# Top.net
KiCad netlist of a schematic drawn in Altium Designer
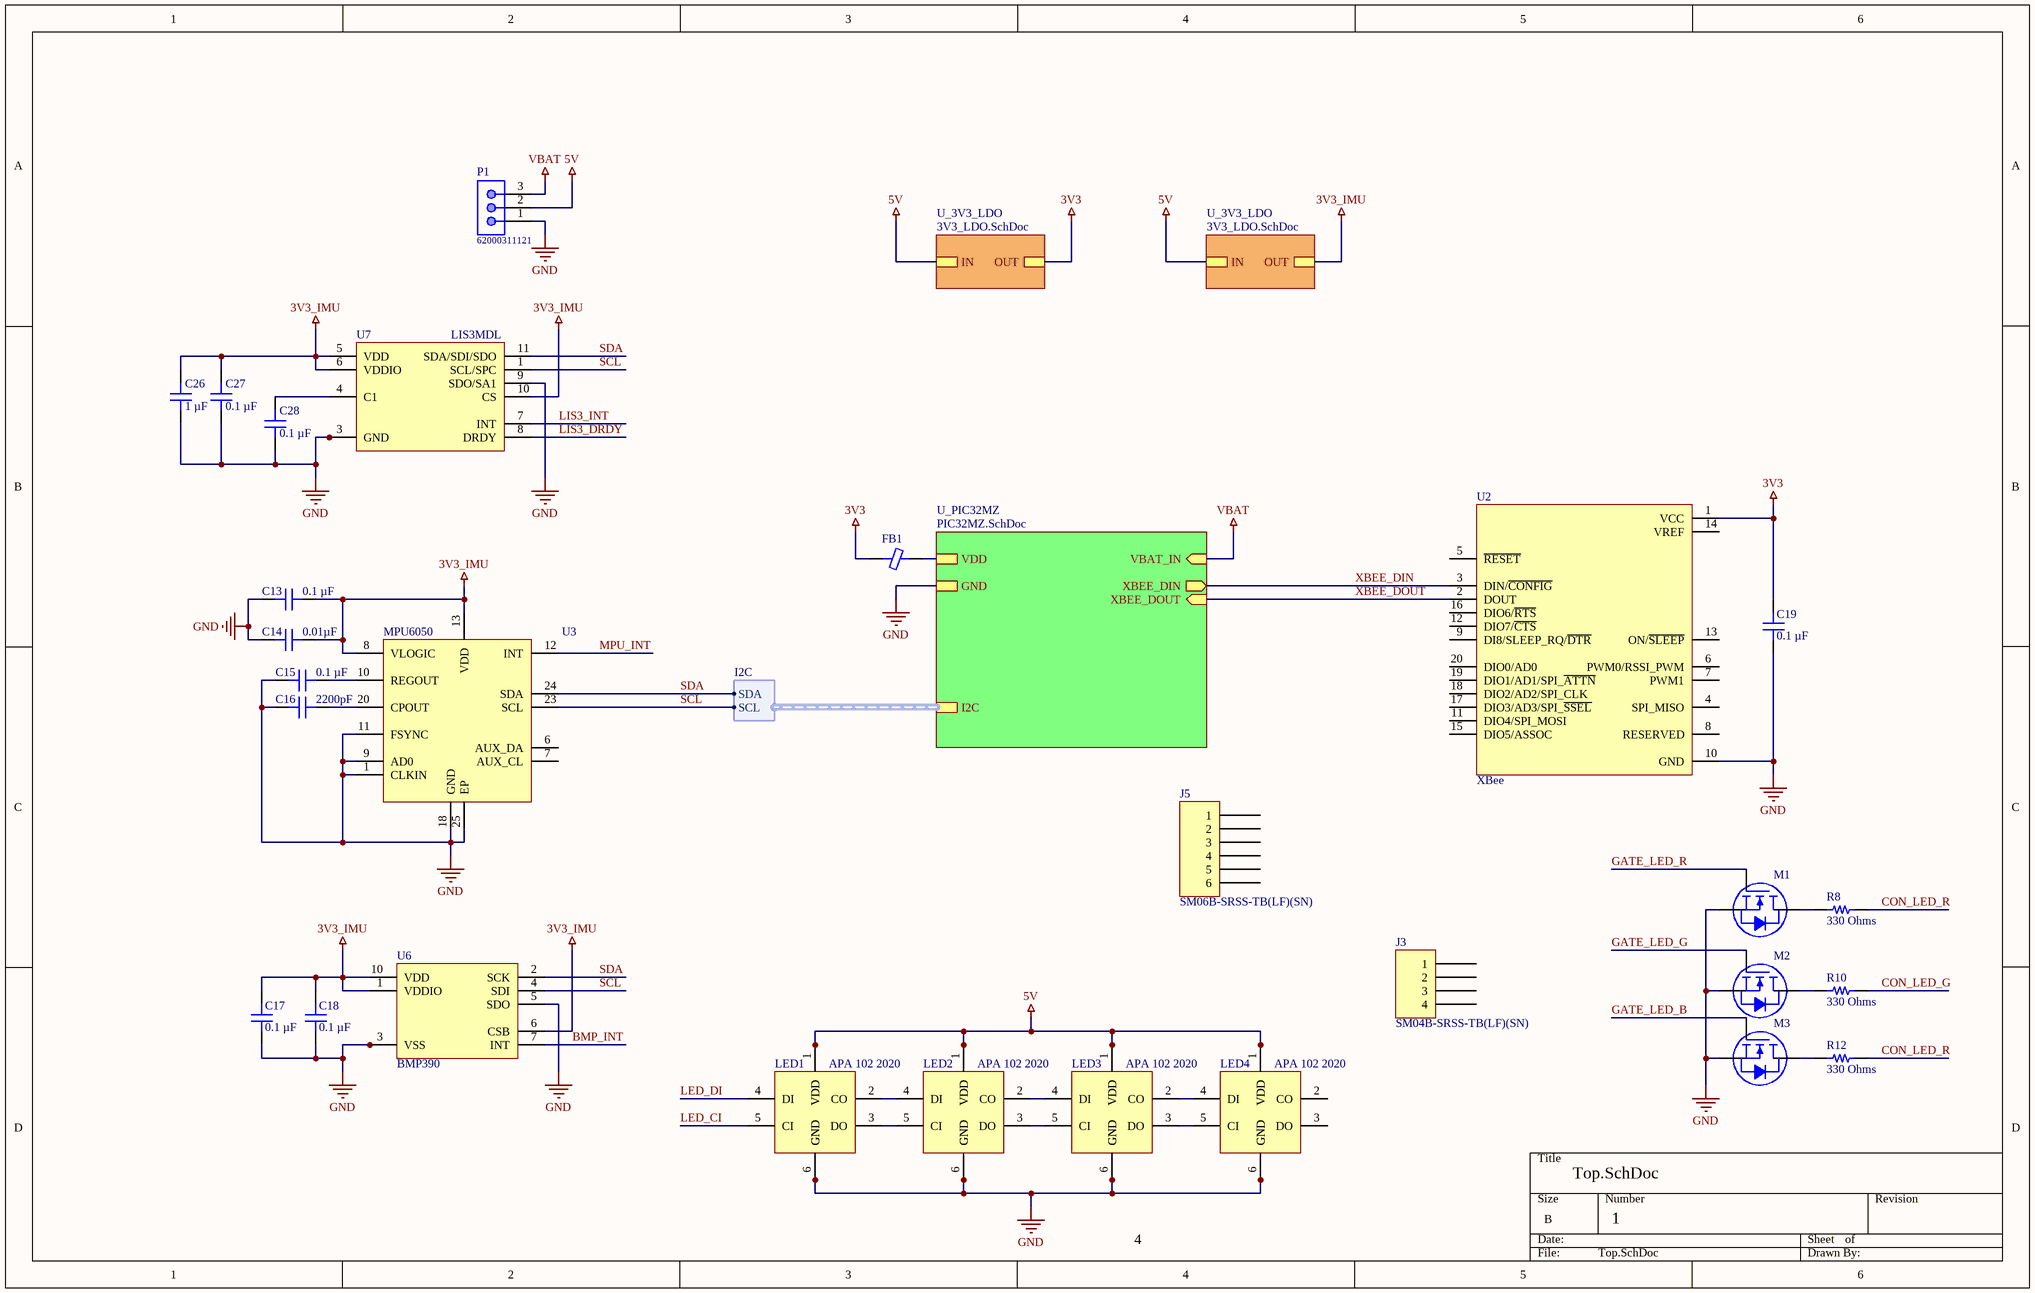
[diagram p0: Top.SchDoc]

(export (version "E")
  (design (tool "Eeschema 10.0.6"))
  (components
    (comp (ref "C13")
      (value "0.1 µF")
      (footprint "CAP 0402_1005")
      (description "CAP CER 0.1UF 16V X7R 0402")
      (fields (field (name "PART NUMBER") "C0402C104K4RACAUTO") (field (name "MANUFACTURER") "KEMET"))
      (libsource (lib "Celestial Altium Library - altium_library") (part "Capacitor"))
    )
    (comp (ref "C14")
      (value "0.01µF")
      (footprint "CAP 0603_1608")
      (description "CAP CER 0.01UF 250V X7R 0603")
      (fields (field (name "PART NUMBER") "C0603C103KARACAUTO") (field (name "MANUFACTURER") "KEMET"))
      (libsource (lib "Celestial Altium Library - altium_library") (part "Capacitor"))
    )
    (comp (ref "C15")
      (value "0.1 µF")
      (footprint "CAP 0402_1005")
      (description "CAP CER 0.1UF 16V X7R 0402")
      (fields (field (name "PART NUMBER") "C0402C104K4RACAUTO") (field (name "MANUFACTURER") "KEMET"))
      (libsource (lib "Celestial Altium Library - altium_library") (part "Capacitor"))
    )
    (comp (ref "C16")
      (value "2200pF")
      (footprint "CAP 0603_1608")
      (description "CAP CER 2200PF 50V 0603 EPOXY")
      (fields
        (field (name "PART NUMBER") "CGA3E2X8R1H222M080AD")
        (field (name "MANUFACTURER") "TDK Corporation")
      )
      (libsource (lib "Celestial Altium Library - altium_library") (part "Capacitor"))
    )
    (comp (ref "C17")
      (value "0.1 µF")
      (footprint "CAP 0402_1005")
      (description "CAP CER 0.1UF 16V X7R 0402")
      (fields (field (name "PART NUMBER") "C0402C104K4RACAUTO") (field (name "MANUFACTURER") "KEMET"))
      (libsource (lib "Celestial Altium Library - altium_library") (part "Capacitor"))
    )
    (comp (ref "C18")
      (value "0.1 µF")
      (footprint "CAP 0402_1005")
      (description "CAP CER 0.1UF 16V X7R 0402")
      (fields (field (name "PART NUMBER") "C0402C104K4RACAUTO") (field (name "MANUFACTURER") "KEMET"))
      (libsource (lib "Celestial Altium Library - altium_library") (part "Capacitor"))
    )
    (comp (ref "C19")
      (value "0.1 µF")
      (footprint "CAP 0402_1005")
      (description "CAP CER 0.1UF 16V X7R 0402")
      (fields (field (name "PART NUMBER") "C0402C104K4RACAUTO") (field (name "MANUFACTURER") "KEMET"))
      (libsource (lib "Celestial Altium Library - altium_library") (part "Capacitor"))
    )
    (comp (ref "C26")
      (value "1 µF")
      (footprint "CAP 0402_1005")
      (description "CAP CER 0.1UF 16V X7R 0402")
      (fields (field (name "PART NUMBER") "C0402C104K4RACAUTO") (field (name "MANUFACTURER") "KEMET"))
      (libsource (lib "Celestial Altium Library - altium_library") (part "Capacitor"))
    )
    (comp (ref "C27")
      (value "0.1 µF")
      (footprint "CAP 0402_1005")
      (description "CAP CER 0.1UF 16V X7R 0402")
      (fields (field (name "PART NUMBER") "C0402C104K4RACAUTO") (field (name "MANUFACTURER") "KEMET"))
      (libsource (lib "Celestial Altium Library - altium_library") (part "Capacitor"))
    )
    (comp (ref "C28")
      (value "0.1 µF")
      (footprint "CAP 0402_1005")
      (description "CAP CER 0.1UF 16V X7R 0402")
      (fields (field (name "PART NUMBER") "C0402C104K4RACAUTO") (field (name "MANUFACTURER") "KEMET"))
      (libsource (lib "Celestial Altium Library - altium_library") (part "Capacitor"))
    )
    (comp (ref "FB1")
      (value "~")
      (footprint "FER 0805_2012")
      (description "FERRITE BEAD 0805 1LN")
      (fields
        (field (name "PART NUMBER") "2508051017Y0")
        (field (name "MANUFACTURER") "Fair-Rite Products Corp.")
      )
      (libsource (lib "Celestial Altium Library - altium_library") (part "Ferrite Chip"))
    )
    (comp (ref "J3")
      (value "SM04B-SRSS-TB(LF)(SN)")
      (footprint "JST SM04B-SRSS-TB")
      (description "CONN HEADER SMD R/A 4POS 1MM")
      (fields (field (name "MANUFACTURER") "JST Sales America Inc."))
      (libsource (lib "Celestial Altium Library - altium_library") (part "4 Pin"))
    )
    (comp (ref "J5")
      (value "SM06B-SRSS-TB(LF)(SN)")
      (footprint "JST SM06B-SRSS-TB")
      (description "CONN HEADER SMD R/A 6POS 1MM")
      (fields (field (name "MANUFACTURER") "JST Sales America Inc."))
      (libsource (lib "Celestial Altium Library - altium_library") (part "6 Pin"))
    )
    (comp (ref "LED1")
      (value "APA 102 2020")
      (footprint "LED_APA-102-2020-256-8")
      (description "8-pin type LED three-color RGB Dimming control")
      (fields (field (name "MP") "APA-102-2020-256-8") (field (name "MF") "iPixel LED Light Co."))
      (libsource (lib "IC") (part "APA-102-2020-256-8"))
    )
    (comp (ref "LED2")
      (value "APA 102 2020")
      (footprint "LED_APA-102-2020-256-8")
      (description "8-pin type LED three-color RGB Dimming control")
      (fields (field (name "MP") "APA-102-2020-256-8") (field (name "MF") "iPixel LED Light Co."))
      (libsource (lib "IC") (part "APA-102-2020-256-8"))
    )
    (comp (ref "LED3")
      (value "APA 102 2020")
      (footprint "LED_APA-102-2020-256-8")
      (description "8-pin type LED three-color RGB Dimming control")
      (fields (field (name "MP") "APA-102-2020-256-8") (field (name "MF") "iPixel LED Light Co."))
      (libsource (lib "IC") (part "APA-102-2020-256-8"))
    )
    (comp (ref "LED4")
      (value "APA 102 2020")
      (footprint "LED_APA-102-2020-256-8")
      (description "8-pin type LED three-color RGB Dimming control")
      (fields (field (name "MP") "APA-102-2020-256-8") (field (name "MF") "iPixel LED Light Co."))
      (libsource (lib "IC") (part "APA-102-2020-256-8"))
    )
    (comp (ref "M1")
      (value "BSS123-7-F")
      (footprint "DIODES SOT-23-3")
      (description "MOSFET N-CH 100V 170MA SOT23-3")
      (fields (field (name "MANUFACTURER") "Diodes Incorporated"))
      (libsource (lib "Celestial Altium Library - altium_library") (part "DIODES INC MOSFET N-CH SOT-23-3"))
    )
    (comp (ref "M2")
      (value "BSS123-7-F")
      (footprint "DIODES SOT-23-3")
      (description "MOSFET N-CH 100V 170MA SOT23-3")
      (fields (field (name "MANUFACTURER") "Diodes Incorporated"))
      (libsource (lib "Celestial Altium Library - altium_library") (part "DIODES INC MOSFET N-CH SOT-23-3"))
    )
    (comp (ref "M3")
      (value "BSS123-7-F")
      (footprint "DIODES SOT-23-3")
      (description "MOSFET N-CH 100V 170MA SOT23-3")
      (fields (field (name "MANUFACTURER") "Diodes Incorporated"))
      (libsource (lib "Celestial Altium Library - altium_library") (part "DIODES INC MOSFET N-CH SOT-23-3"))
    )
    (comp (ref "P1")
      (value "62000311121")
      (footprint "62000311121")
      (description "WR-PHD Pin Header, THT, pitch 2mm, Single Row, Vertical, 3p")
      (fields (field (name "MANUFACTURER") "Wurth Elektronik"))
      (libsource (lib "Altium_WR-PHD") (part "62000311121"))
    )
    (comp (ref "R8")
      (value "330 Ohms")
      (footprint "RES 0603_1608")
      (description "RES 10K OHM 0.1% 1/16W 0603")
      (fields
        (field (name "PART NUMBER") "RNCS0603BKE10K0")
        (field (name "MANUFACTURER") "Stackpole Electronics Inc")
      )
      (libsource (lib "Celestial Altium Library - altium_library") (part "Resistor"))
    )
    (comp (ref "R10")
      (value "330 Ohms")
      (footprint "RES 0603_1608")
      (description "RES 10K OHM 0.1% 1/16W 0603")
      (fields
        (field (name "PART NUMBER") "RNCS0603BKE10K0")
        (field (name "MANUFACTURER") "Stackpole Electronics Inc")
      )
      (libsource (lib "Celestial Altium Library - altium_library") (part "Resistor"))
    )
    (comp (ref "R12")
      (value "330 Ohms")
      (footprint "RES 0603_1608")
      (description "RES 10K OHM 0.1% 1/16W 0603")
      (fields
        (field (name "PART NUMBER") "RNCS0603BKE10K0")
        (field (name "MANUFACTURER") "Stackpole Electronics Inc")
      )
      (libsource (lib "Celestial Altium Library - altium_library") (part "Resistor"))
    )
    (comp (ref "U2")
      (value "XBee")
      (footprint "XBee -SMD Header")
      (description "802.15.4 Transceiver Module 2.4GHz Antenna Not Included, U.FL Through Hole")
      (libsource (lib "IC") (part "XBee SMD Header"))
    )
    (comp (ref "U3") (value "MPU6050") (footprint "IC_MPU6050") (libsource (lib "IC") (part "MPU6050")))
    (comp (ref "U6")
      (value "BMP390")
      (footprint "BMP390L")
      (description "Altimeter")
      (libsource (lib "IC") (part "BMP390"))
    )
    (comp (ref "U7")
      (value "LIS3MDL")
      (footprint "LGA12_ST")
      (description "Magnetometer")
      (libsource (lib "IC") (part "LIS3MDL"))
    )
  )
  (nets
    (net (code "2") (name "/BMP_INT") (class "Default")
      (node (ref "U6") (pin "7") (pinfunction "INT_7") (pintype "passive"))
    )
    (net (code "3") (name "/CON_LED_G") (class "Default")
      (node (ref "R10") (pin "2") (pinfunction "2_2") (pintype "passive"))
    )
    (net (code "4") (name "/CON_LED_R") (class "Default")
      (node (ref "R12") (pin "2") (pinfunction "2_2") (pintype "passive"))
      (node (ref "R8") (pin "2") (pinfunction "2_2") (pintype "passive"))
    )
    (net (code "5") (name "/GATE_LED_B") (class "Default")
      (node (ref "M3") (pin "1") (pinfunction "G_1") (pintype "passive"))
    )
    (net (code "6") (name "/GATE_LED_G") (class "Default")
      (node (ref "M2") (pin "1") (pinfunction "G_1") (pintype "passive"))
    )
    (net (code "7") (name "/GATE_LED_R") (class "Default")
      (node (ref "M1") (pin "1") (pinfunction "G_1") (pintype "passive"))
    )
    (net (code "8") (name "/LED_CI") (class "Default")
      (node (ref "LED1") (pin "5") (pinfunction "CI_5") (pintype "passive"))
    )
    (net (code "9") (name "/LED_DI") (class "Default")
      (node (ref "LED1") (pin "4") (pinfunction "DI_4") (pintype "passive"))
    )
    (net (code "10") (name "/LIS3_DRDY") (class "Default")
      (node (ref "U7") (pin "8") (pinfunction "DRDY_8") (pintype "passive"))
    )
    (net (code "11") (name "/LIS3_INT") (class "Default")
      (node (ref "U7") (pin "7") (pinfunction "INT_7") (pintype "passive"))
    )
    (net (code "12") (name "/MPU_INT") (class "Default")
      (node (ref "U3") (pin "12") (pinfunction "INT_12") (pintype "passive"))
    )
    (net (code "13") (name "/SCL") (class "Default")
      (node (ref "U3") (pin "23") (pinfunction "SCL_23") (pintype "passive"))
      (node (ref "U6") (pin "4") (pinfunction "SDI_4") (pintype "passive"))
      (node (ref "U7") (pin "1") (pinfunction "SCL/SPC_1") (pintype "passive"))
    )
    (net (code "14") (name "/SDA") (class "Default")
      (node (ref "U3") (pin "24") (pinfunction "SDA_24") (pintype "passive"))
      (node (ref "U6") (pin "2") (pinfunction "SCK_2") (pintype "passive"))
      (node (ref "U7") (pin "11") (pinfunction "SDA/SDI/SDO_11") (pintype "passive"))
    )
    (net (code "15") (name "/VDD") (class "Default")
      (node (ref "FB1") (pin "2") (pinfunction "2_2") (pintype "passive"))
    )
    (net (code "16") (name "/XBEE_DIN") (class "Default")
      (node (ref "U2") (pin "3") (pinfunction "DIN/~{CONFIG}_3") (pintype "passive"))
    )
    (net (code "17") (name "/XBEE_DOUT") (class "Default")
      (node (ref "U2") (pin "2") (pinfunction "DOUT_2") (pintype "passive"))
    )
    (net (code "19") (name "3V3") (class "Default")
      (node (ref "C19") (pin "2") (pinfunction "2_2") (pintype "passive"))
      (node (ref "FB1") (pin "1") (pinfunction "1_1") (pintype "passive"))
      (node (ref "U2") (pin "1") (pinfunction "VCC_1") (pintype "power_in"))
    )
    (net (code "20") (name "3V3_IMU") (class "Default")
      (node (ref "C13") (pin "1") (pinfunction "1_1") (pintype "passive"))
      (node (ref "C14") (pin "2") (pinfunction "2_2") (pintype "passive"))
      (node (ref "C17") (pin "2") (pinfunction "2_2") (pintype "passive"))
      (node (ref "C18") (pin "2") (pinfunction "2_2") (pintype "passive"))
      (node (ref "C26") (pin "1") (pinfunction "1_1") (pintype "passive"))
      (node (ref "C27") (pin "1") (pinfunction "1_1") (pintype "passive"))
      (node (ref "U3") (pin "13") (pinfunction "VDD_13") (pintype "passive"))
      (node (ref "U3") (pin "8") (pinfunction "VLOGIC_8") (pintype "passive"))
      (node (ref "U6") (pin "1") (pinfunction "VDDIO_1") (pintype "passive"))
      (node (ref "U6") (pin "10") (pinfunction "VDD_10") (pintype "passive"))
      (node (ref "U6") (pin "6") (pinfunction "CSB_6") (pintype "passive"))
      (node (ref "U7") (pin "10") (pinfunction "CS_10") (pintype "passive"))
      (node (ref "U7") (pin "5") (pinfunction "VDD_5") (pintype "passive"))
      (node (ref "U7") (pin "6") (pinfunction "VDDIO_6") (pintype "passive"))
    )
    (net (code "21") (name "5V") (class "Default")
      (node (ref "LED1") (pin "1") (pinfunction "VDD_1") (pintype "power_in"))
      (node (ref "LED1") (pin "8") (pinfunction "VDD_8") (pintype "power_in"))
      (node (ref "LED2") (pin "1") (pinfunction "VDD_1") (pintype "power_in"))
      (node (ref "LED2") (pin "8") (pinfunction "VDD_8") (pintype "power_in"))
      (node (ref "LED3") (pin "1") (pinfunction "VDD_1") (pintype "power_in"))
      (node (ref "LED3") (pin "8") (pinfunction "VDD_8") (pintype "power_in"))
      (node (ref "LED4") (pin "1") (pinfunction "VDD_1") (pintype "power_in"))
      (node (ref "LED4") (pin "8") (pinfunction "VDD_8") (pintype "power_in"))
      (node (ref "P1") (pin "2") (pinfunction "2_2") (pintype "passive"))
    )
    (net (code "22") (name "GND") (class "Default")
      (node (ref "C13") (pin "2") (pinfunction "2_2") (pintype "passive"))
      (node (ref "C14") (pin "1") (pinfunction "1_1") (pintype "passive"))
      (node (ref "C15") (pin "2") (pinfunction "2_2") (pintype "passive"))
      (node (ref "C16") (pin "2") (pinfunction "2_2") (pintype "passive"))
      (node (ref "C17") (pin "1") (pinfunction "1_1") (pintype "passive"))
      (node (ref "C18") (pin "1") (pinfunction "1_1") (pintype "passive"))
      (node (ref "C19") (pin "1") (pinfunction "1_1") (pintype "passive"))
      (node (ref "C26") (pin "2") (pinfunction "2_2") (pintype "passive"))
      (node (ref "C27") (pin "2") (pinfunction "2_2") (pintype "passive"))
      (node (ref "C28") (pin "2") (pinfunction "2_2") (pintype "passive"))
      (node (ref "LED1") (pin "6") (pinfunction "GND_6") (pintype "power_in"))
      (node (ref "LED1") (pin "7") (pinfunction "GND_7") (pintype "power_in"))
      (node (ref "LED2") (pin "6") (pinfunction "GND_6") (pintype "power_in"))
      (node (ref "LED2") (pin "7") (pinfunction "GND_7") (pintype "power_in"))
      (node (ref "LED3") (pin "6") (pinfunction "GND_6") (pintype "power_in"))
      (node (ref "LED3") (pin "7") (pinfunction "GND_7") (pintype "power_in"))
      (node (ref "LED4") (pin "6") (pinfunction "GND_6") (pintype "power_in"))
      (node (ref "LED4") (pin "7") (pinfunction "GND_7") (pintype "power_in"))
      (node (ref "M1") (pin "2") (pinfunction "S_2") (pintype "passive"))
      (node (ref "M2") (pin "2") (pinfunction "S_2") (pintype "passive"))
      (node (ref "M3") (pin "2") (pinfunction "S_2") (pintype "passive"))
      (node (ref "P1") (pin "1") (pinfunction "1_1") (pintype "passive"))
      (node (ref "U2") (pin "10") (pinfunction "GND_10") (pintype "power_in"))
      (node (ref "U3") (pin "1") (pinfunction "CLKIN_1") (pintype "passive"))
      (node (ref "U3") (pin "11") (pinfunction "FSYNC_11") (pintype "passive"))
      (node (ref "U3") (pin "18") (pinfunction "GND_18") (pintype "passive"))
      (node (ref "U3") (pin "25") (pinfunction "EP_25") (pintype "passive"))
      (node (ref "U3") (pin "9") (pinfunction "AD0_9") (pintype "passive"))
      (node (ref "U6") (pin "3") (pinfunction "VSS_3") (pintype "passive"))
      (node (ref "U6") (pin "5") (pinfunction "SDO_5") (pintype "passive"))
      (node (ref "U6") (pin "8") (pinfunction "VSS_8") (pintype "passive"))
      (node (ref "U6") (pin "9") (pinfunction "VSS_9") (pintype "passive"))
      (node (ref "U7") (pin "12") (pinfunction "Reserved_12") (pintype "passive"))
      (node (ref "U7") (pin "2") (pinfunction "Reserved_2") (pintype "passive"))
      (node (ref "U7") (pin "3") (pinfunction "GND_3") (pintype "passive"))
      (node (ref "U7") (pin "9") (pinfunction "SDO/SA1_9") (pintype "passive"))
    )
    (net (code "23") (name "Net-(LED1-CO)") (class "Default")
      (node (ref "LED1") (pin "2") (pinfunction "CO_2") (pintype "passive"))
      (node (ref "LED2") (pin "4") (pinfunction "DI_4") (pintype "passive"))
    )
    (net (code "24") (name "Net-(LED1-DO)") (class "Default")
      (node (ref "LED1") (pin "3") (pinfunction "DO_3") (pintype "passive"))
      (node (ref "LED2") (pin "5") (pinfunction "CI_5") (pintype "passive"))
    )
    (net (code "25") (name "Net-(LED2-CO)") (class "Default")
      (node (ref "LED2") (pin "2") (pinfunction "CO_2") (pintype "passive"))
      (node (ref "LED3") (pin "4") (pinfunction "DI_4") (pintype "passive"))
    )
    (net (code "26") (name "Net-(LED2-DO)") (class "Default")
      (node (ref "LED2") (pin "3") (pinfunction "DO_3") (pintype "passive"))
      (node (ref "LED3") (pin "5") (pinfunction "CI_5") (pintype "passive"))
    )
    (net (code "27") (name "Net-(LED3-CO)") (class "Default")
      (node (ref "LED3") (pin "2") (pinfunction "CO_2") (pintype "passive"))
      (node (ref "LED4") (pin "4") (pinfunction "DI_4") (pintype "passive"))
    )
    (net (code "28") (name "Net-(LED3-DO)") (class "Default")
      (node (ref "LED3") (pin "3") (pinfunction "DO_3") (pintype "passive"))
      (node (ref "LED4") (pin "5") (pinfunction "CI_5") (pintype "passive"))
    )
    (net (code "29") (name "Net-(M1-D)") (class "Default")
      (node (ref "M1") (pin "3") (pinfunction "D_3") (pintype "passive"))
      (node (ref "R8") (pin "1") (pinfunction "1_1") (pintype "passive"))
    )
    (net (code "30") (name "Net-(M2-D)") (class "Default")
      (node (ref "M2") (pin "3") (pinfunction "D_3") (pintype "passive"))
      (node (ref "R10") (pin "1") (pinfunction "1_1") (pintype "passive"))
    )
    (net (code "31") (name "Net-(M3-D)") (class "Default")
      (node (ref "M3") (pin "3") (pinfunction "D_3") (pintype "passive"))
      (node (ref "R12") (pin "1") (pinfunction "1_1") (pintype "passive"))
    )
    (net (code "32") (name "Net-(U3-CPOUT)") (class "Default")
      (node (ref "C16") (pin "1") (pinfunction "1_1") (pintype "passive"))
      (node (ref "U3") (pin "20") (pinfunction "CPOUT_20") (pintype "passive"))
    )
    (net (code "33") (name "Net-(U3-REGOUT)") (class "Default")
      (node (ref "C15") (pin "1") (pinfunction "1_1") (pintype "passive"))
      (node (ref "U3") (pin "10") (pinfunction "REGOUT_10") (pintype "passive"))
    )
    (net (code "34") (name "Net-(U7-C1)") (class "Default")
      (node (ref "C28") (pin "1") (pinfunction "1_1") (pintype "passive"))
      (node (ref "U7") (pin "4") (pinfunction "C1_4") (pintype "passive"))
    )
    (net (code "35") (name "VBAT") (class "Default")
      (node (ref "P1") (pin "3") (pinfunction "3_3") (pintype "passive"))
    )
    (net (code "36") (name "unconnected-(J3-Pad1)") (class "Default")
      (node (ref "J3") (pin "1") (pinfunction "1_1") (pintype "passive"))
    )
    (net (code "37") (name "unconnected-(J3-Pad2)") (class "Default")
      (node (ref "J3") (pin "2") (pinfunction "2_2") (pintype "passive"))
    )
    (net (code "38") (name "unconnected-(J3-Pad3)") (class "Default")
      (node (ref "J3") (pin "3") (pinfunction "3_3") (pintype "passive"))
    )
    (net (code "39") (name "unconnected-(J3-Pad4)") (class "Default")
      (node (ref "J3") (pin "4") (pinfunction "4_4") (pintype "passive"))
    )
    (net (code "40") (name "unconnected-(J5-Pad1)") (class "Default")
      (node (ref "J5") (pin "1") (pinfunction "1_1") (pintype "passive"))
    )
    (net (code "41") (name "unconnected-(J5-Pad2)") (class "Default")
      (node (ref "J5") (pin "2") (pinfunction "2_2") (pintype "passive"))
    )
    (net (code "42") (name "unconnected-(J5-Pad3)") (class "Default")
      (node (ref "J5") (pin "3") (pinfunction "3_3") (pintype "passive"))
    )
    (net (code "43") (name "unconnected-(J5-Pad4)") (class "Default")
      (node (ref "J5") (pin "4") (pinfunction "4_4") (pintype "passive"))
    )
    (net (code "44") (name "unconnected-(J5-Pad5)") (class "Default")
      (node (ref "J5") (pin "5") (pinfunction "5_5") (pintype "passive"))
    )
    (net (code "45") (name "unconnected-(J5-Pad6)") (class "Default")
      (node (ref "J5") (pin "6") (pinfunction "6_6") (pintype "passive"))
    )
    (net (code "46") (name "unconnected-(LED4-CO-Pad2)") (class "Default")
      (node (ref "LED4") (pin "2") (pinfunction "CO_2") (pintype "passive"))
    )
    (net (code "47") (name "unconnected-(LED4-DO-Pad3)") (class "Default")
      (node (ref "LED4") (pin "3") (pinfunction "DO_3") (pintype "passive"))
    )
    (net (code "48") (name "unconnected-(U2-DI8{slash}SLEEP_RQ{slash}~{DTR}-Pad9)") (class "Default")
      (node (ref "U2") (pin "9") (pinfunction "DI8/SLEEP_RQ/~{DTR}_9") (pintype "passive"))
    )
    (net (code "49") (name "unconnected-(U2-DIO0{slash}AD0-Pad20)") (class "Default")
      (node (ref "U2") (pin "20") (pinfunction "DIO0/AD0_20") (pintype "passive"))
    )
    (net (code "50") (name "unconnected-(U2-DIO1{slash}AD1{slash}SPI_~{ATTN}-Pad19)") (class "Default")
      (node (ref "U2") (pin "19") (pinfunction "DIO1/AD1/SPI_~{ATTN}_19") (pintype "passive"))
    )
    (net (code "51") (name "unconnected-(U2-DIO2{slash}AD2{slash}SPI_CLK-Pad18)") (class "Default")
      (node (ref "U2") (pin "18") (pinfunction "DIO2/AD2/SPI_CLK_18") (pintype "passive"))
    )
    (net (code "52") (name "unconnected-(U2-DIO3{slash}AD3{slash}SPI_~{SSEL}-Pad17)") (class "Default")
      (node (ref "U2") (pin "17") (pinfunction "DIO3/AD3/SPI_~{SSEL}_17") (pintype "passive"))
    )
    (net (code "53") (name "unconnected-(U2-DIO4{slash}SPI_MOSI-Pad11)") (class "Default")
      (node (ref "U2") (pin "11") (pinfunction "DIO4/SPI_MOSI_11") (pintype "passive"))
    )
    (net (code "54") (name "unconnected-(U2-DIO5{slash}ASSOC-Pad15)") (class "Default")
      (node (ref "U2") (pin "15") (pinfunction "DIO5/ASSOC_15") (pintype "passive"))
    )
    (net (code "55") (name "unconnected-(U2-DIO6{slash}~{RTS}-Pad16)") (class "Default")
      (node (ref "U2") (pin "16") (pinfunction "DIO6/~{RTS}_16") (pintype "passive"))
    )
    (net (code "56") (name "unconnected-(U2-DIO7{slash}~{CTS}-Pad12)") (class "Default")
      (node (ref "U2") (pin "12") (pinfunction "DIO7/~{CTS}_12") (pintype "passive"))
    )
    (net (code "57") (name "unconnected-(U2-ON{slash}~{SLEEP}-Pad13)") (class "Default")
      (node (ref "U2") (pin "13") (pinfunction "ON/~{SLEEP}_13") (pintype "passive"))
    )
    (net (code "58") (name "unconnected-(U2-PWM0{slash}RSSI_PWM-Pad6)") (class "Default")
      (node (ref "U2") (pin "6") (pinfunction "PWM0/RSSI_PWM_6") (pintype "passive"))
    )
    (net (code "59") (name "unconnected-(U2-PWM1-Pad7)") (class "Default")
      (node (ref "U2") (pin "7") (pinfunction "PWM1_7") (pintype "passive"))
    )
    (net (code "60") (name "unconnected-(U2-RESERVED-Pad8)") (class "Default")
      (node (ref "U2") (pin "8") (pinfunction "RESERVED_8") (pintype "passive"))
    )
    (net (code "61") (name "unconnected-(U2-SPI_MISO-Pad4)") (class "Default")
      (node (ref "U2") (pin "4") (pinfunction "SPI_MISO_4") (pintype "passive"))
    )
    (net (code "62") (name "unconnected-(U2-VREF-Pad14)") (class "Default")
      (node (ref "U2") (pin "14") (pinfunction "VREF_14") (pintype "power_in"))
    )
    (net (code "63") (name "unconnected-(U2-~{RESET}-Pad5)") (class "Default")
      (node (ref "U2") (pin "5") (pinfunction "~{RESET}_5") (pintype "passive"))
    )
    (net (code "64") (name "unconnected-(U3-AUX_CL-Pad7)") (class "Default")
      (node (ref "U3") (pin "7") (pinfunction "AUX_CL_7") (pintype "passive"))
    )
    (net (code "65") (name "unconnected-(U3-AUX_DA-Pad6)") (class "Default")
      (node (ref "U3") (pin "6") (pinfunction "AUX_DA_6") (pintype "passive"))
    )
  )
)
